# tssop24.net
KiCad netlist of a schematic drawn in EAGLE
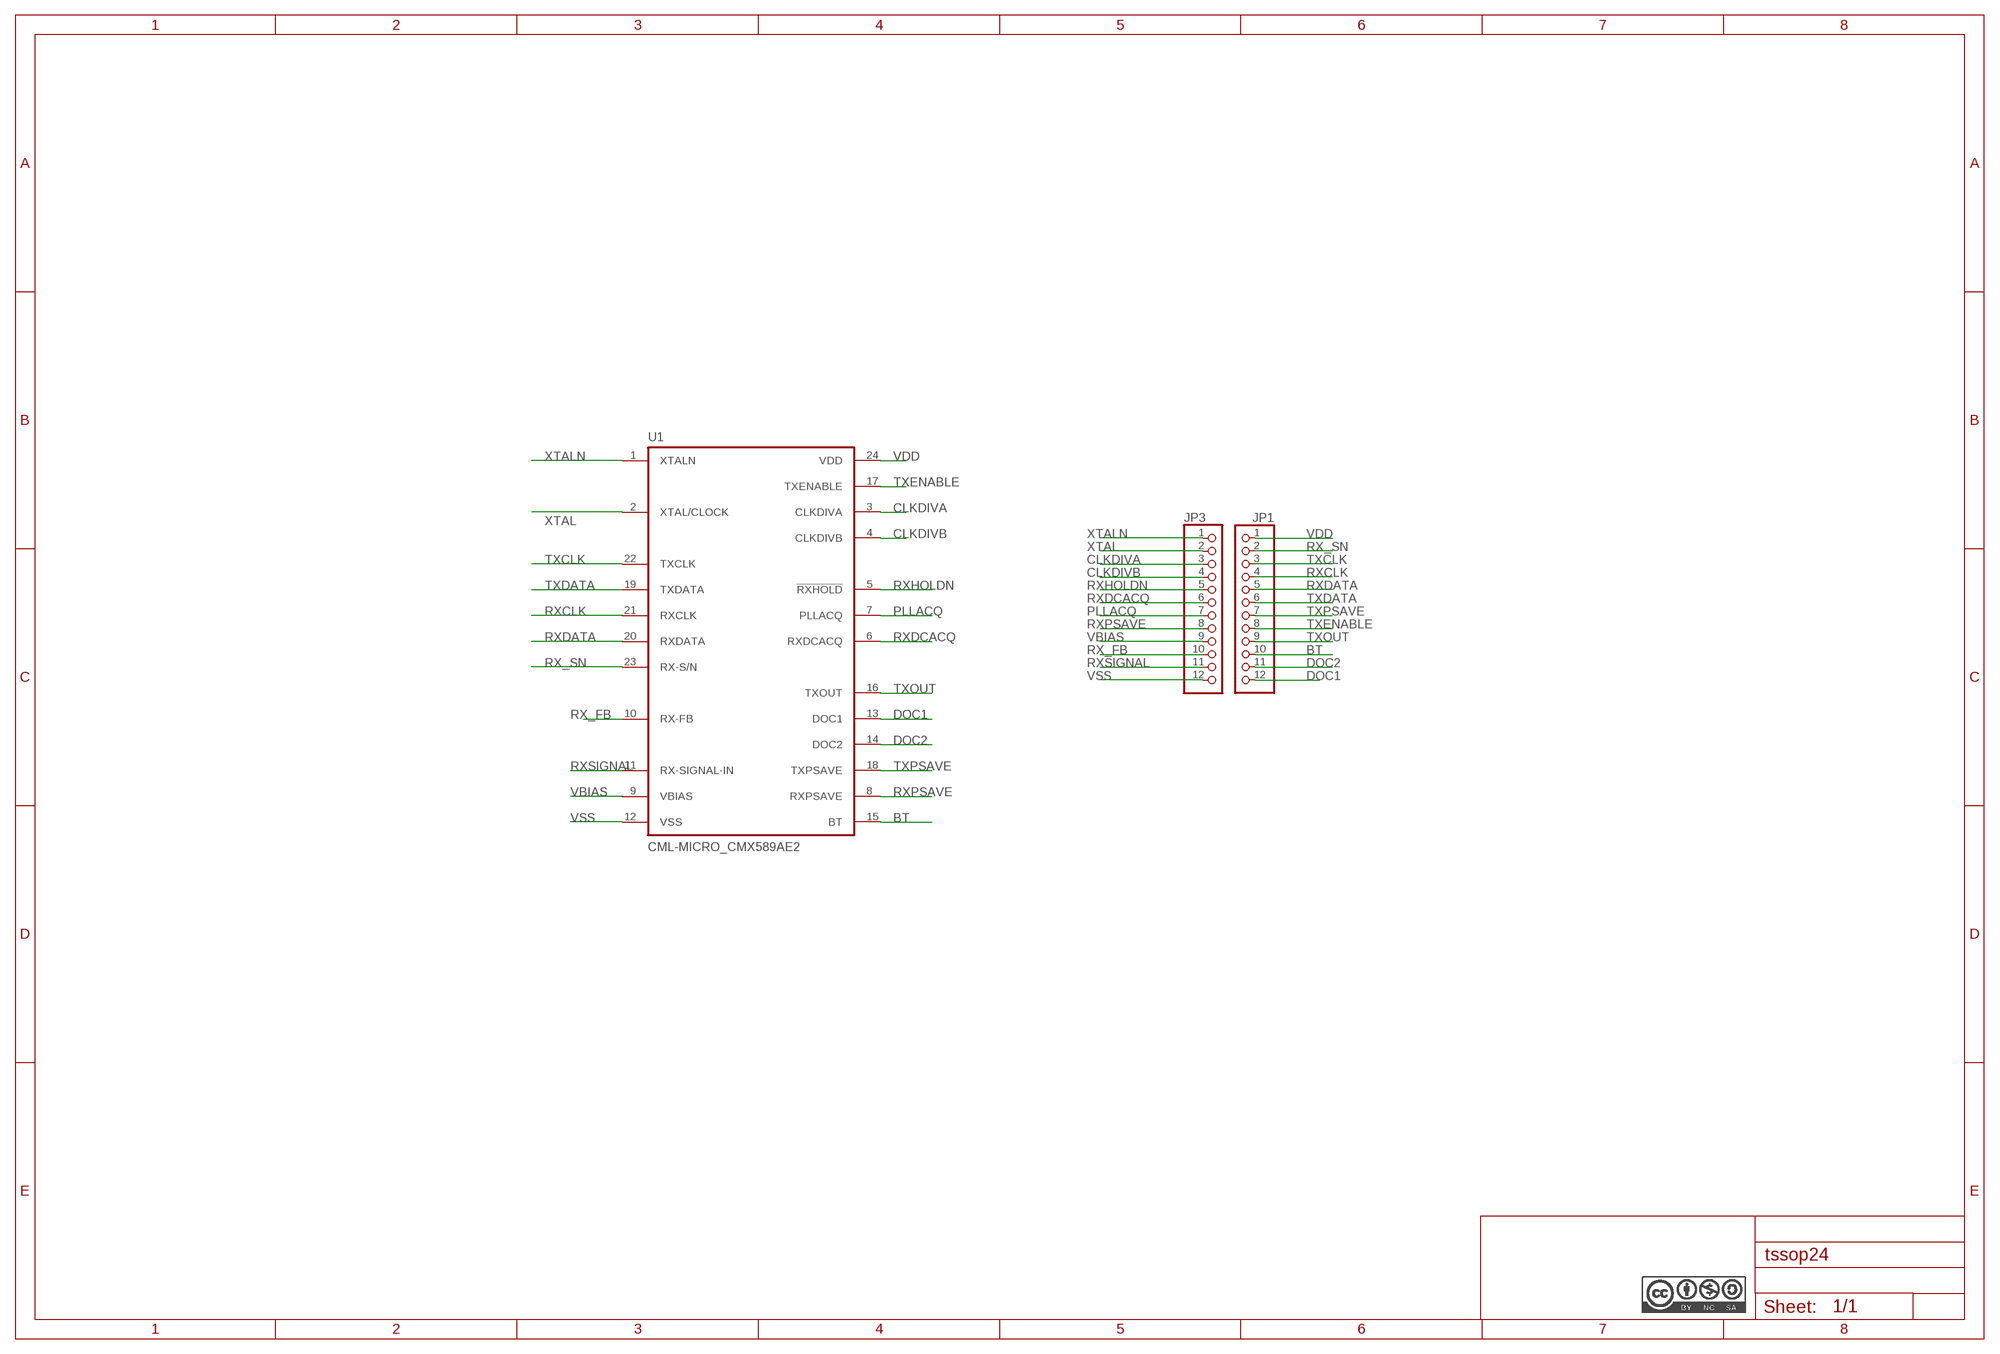
[diagram p0: schematic, sheet 1]

(export (version "E")
  (design (tool "Eeschema 10.0.6"))
  (components
    (comp (ref "JP1")
      (value "PINHD-1X12-CB")
      (footprint "eagle-import:1X12-CB")
      (libsource (lib "eagle-import") (part "PINHD-1X12-CB"))
    )
    (comp (ref "JP3")
      (value "PINHD-1X12-CB")
      (footprint "eagle-import:1X12-CB")
      (libsource (lib "eagle-import") (part "PINHD-1X12-CB"))
    )
    (comp (ref "U1")
      (value "CML-MICRO_CMX589AE2")
      (footprint "eagle-import:AIS_MK2_CML-MICRO_TSSOP24")
      (libsource (lib "eagle-import") (part "AIS_MK2_CML-MICRO_CMX589AE2"))
    )
  )
  (nets
    (net (code "1") (name "/BT") (class "Default")
      (node (ref "JP1") (pin "10") (pinfunction "10_10") (pintype "passive"))
      (node (ref "U1") (pin "15") (pinfunction "BT_15") (pintype "input"))
    )
    (net (code "2") (name "/CLKDIVA") (class "Default")
      (node (ref "JP3") (pin "3") (pinfunction "3_3") (pintype "passive"))
      (node (ref "U1") (pin "3") (pinfunction "CLKDIVA_3") (pintype "input"))
    )
    (net (code "3") (name "/CLKDIVB") (class "Default")
      (node (ref "JP3") (pin "4") (pinfunction "4_4") (pintype "passive"))
      (node (ref "U1") (pin "4") (pinfunction "CLKDIVB_4") (pintype "input"))
    )
    (net (code "4") (name "/DOC1") (class "Default")
      (node (ref "JP1") (pin "12") (pinfunction "12_12") (pintype "passive"))
      (node (ref "U1") (pin "13") (pinfunction "DOC1_13") (pintype "passive"))
    )
    (net (code "5") (name "/DOC2") (class "Default")
      (node (ref "JP1") (pin "11") (pinfunction "11_11") (pintype "passive"))
      (node (ref "U1") (pin "14") (pinfunction "DOC2_14") (pintype "passive"))
    )
    (net (code "6") (name "/PLLACQ") (class "Default")
      (node (ref "JP3") (pin "7") (pinfunction "7_7") (pintype "passive"))
      (node (ref "U1") (pin "7") (pinfunction "PLLACQ_7") (pintype "input"))
    )
    (net (code "7") (name "/RXCLK") (class "Default")
      (node (ref "JP1") (pin "4") (pinfunction "4_4") (pintype "passive"))
      (node (ref "U1") (pin "21") (pinfunction "RXCLK_21") (pintype "output"))
    )
    (net (code "8") (name "/RXDATA") (class "Default")
      (node (ref "JP1") (pin "5") (pinfunction "5_5") (pintype "passive"))
      (node (ref "U1") (pin "20") (pinfunction "RXDATA_20") (pintype "output"))
    )
    (net (code "9") (name "/RXDCACQ") (class "Default")
      (node (ref "JP3") (pin "6") (pinfunction "6_6") (pintype "passive"))
      (node (ref "U1") (pin "6") (pinfunction "RXDCACQ_6") (pintype "input"))
    )
    (net (code "10") (name "/RXHOLDN") (class "Default")
      (node (ref "JP3") (pin "5") (pinfunction "5_5") (pintype "passive"))
      (node (ref "U1") (pin "5") (pinfunction "~{RXHOLD}_5") (pintype "input"))
    )
    (net (code "11") (name "/RXPSAVE") (class "Default")
      (node (ref "JP3") (pin "8") (pinfunction "8_8") (pintype "passive"))
      (node (ref "U1") (pin "8") (pinfunction "RXPSAVE_8") (pintype "input"))
    )
    (net (code "12") (name "/RXSIGNAL") (class "Default")
      (node (ref "JP3") (pin "11") (pinfunction "11_11") (pintype "passive"))
      (node (ref "U1") (pin "11") (pinfunction "RX-SIGNAL-IN_11") (pintype "input"))
    )
    (net (code "13") (name "/RX_FB") (class "Default")
      (node (ref "JP3") (pin "10") (pinfunction "10_10") (pintype "passive"))
      (node (ref "U1") (pin "10") (pinfunction "RX-FB_10") (pintype "input"))
    )
    (net (code "14") (name "/RX_SN") (class "Default")
      (node (ref "JP1") (pin "2") (pinfunction "2_2") (pintype "passive"))
      (node (ref "U1") (pin "23") (pinfunction "RX-S/N_23") (pintype "output"))
    )
    (net (code "15") (name "/TXCLK") (class "Default")
      (node (ref "JP1") (pin "3") (pinfunction "3_3") (pintype "passive"))
      (node (ref "U1") (pin "22") (pinfunction "TXCLK_22") (pintype "output"))
    )
    (net (code "16") (name "/TXDATA") (class "Default")
      (node (ref "JP1") (pin "6") (pinfunction "6_6") (pintype "passive"))
      (node (ref "U1") (pin "19") (pinfunction "TXDATA_19") (pintype "input"))
    )
    (net (code "17") (name "/TXENABLE") (class "Default")
      (node (ref "JP1") (pin "8") (pinfunction "8_8") (pintype "passive"))
      (node (ref "U1") (pin "17") (pinfunction "TXENABLE_17") (pintype "input"))
    )
    (net (code "18") (name "/TXOUT") (class "Default")
      (node (ref "JP1") (pin "9") (pinfunction "9_9") (pintype "passive"))
      (node (ref "U1") (pin "16") (pinfunction "TXOUT_16") (pintype "output"))
    )
    (net (code "19") (name "/TXPSAVE") (class "Default")
      (node (ref "JP1") (pin "7") (pinfunction "7_7") (pintype "passive"))
      (node (ref "U1") (pin "18") (pinfunction "TXPSAVE_18") (pintype "input"))
    )
    (net (code "20") (name "/VBIAS") (class "Default")
      (node (ref "JP3") (pin "9") (pinfunction "9_9") (pintype "passive"))
      (node (ref "U1") (pin "9") (pinfunction "VBIAS_9") (pintype "input"))
    )
    (net (code "21") (name "/VDD") (class "Default")
      (node (ref "JP1") (pin "1") (pinfunction "1_1") (pintype "passive"))
      (node (ref "U1") (pin "24") (pinfunction "VDD_24") (pintype "power_in"))
    )
    (net (code "22") (name "/VSS") (class "Default")
      (node (ref "JP3") (pin "12") (pinfunction "12_12") (pintype "passive"))
      (node (ref "U1") (pin "12") (pinfunction "VSS_12") (pintype "power_in"))
    )
    (net (code "23") (name "/XTAL") (class "Default")
      (node (ref "JP3") (pin "2") (pinfunction "2_2") (pintype "passive"))
      (node (ref "U1") (pin "2") (pinfunction "XTAL/CLOCK_2") (pintype "input"))
    )
    (net (code "24") (name "/XTALN") (class "Default")
      (node (ref "JP3") (pin "1") (pinfunction "1_1") (pintype "passive"))
      (node (ref "U1") (pin "1") (pinfunction "XTALN_1") (pintype "output"))
    )
  )
)
